# comm_sensing.net
KiCad netlist of a schematic drawn in Altium Designer
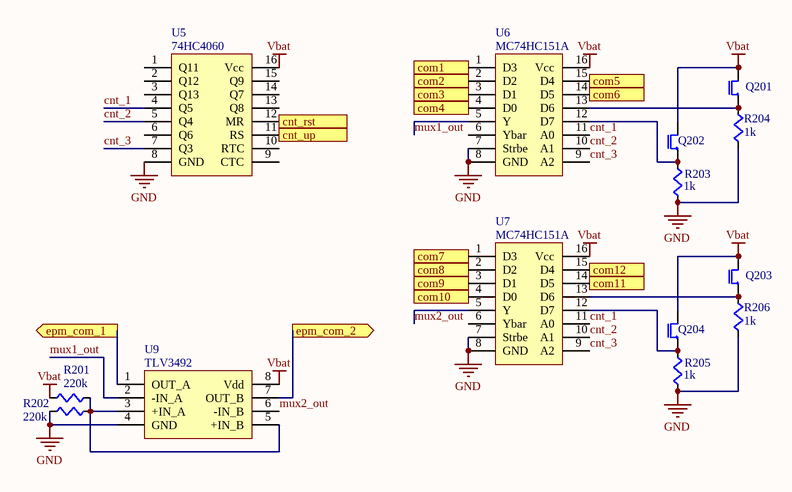
[diagram p0: comm_sensing.SchDoc]

(export (version "E")
  (design (tool "Eeschema 10.0.6"))
  (components
    (comp (ref "Q201")
      (value "PHOTOTRANS")
      (footprint "smd_phototrans")
      (libsource (lib "Components") (part "PHOTOTRANS"))
    )
    (comp (ref "Q202")
      (value "PHOTOTRANS")
      (footprint "smd_phototrans")
      (libsource (lib "Components") (part "PHOTOTRANS"))
    )
    (comp (ref "Q203")
      (value "PHOTOTRANS")
      (footprint "smd_phototrans")
      (libsource (lib "Components") (part "PHOTOTRANS"))
    )
    (comp (ref "Q204")
      (value "PHOTOTRANS")
      (footprint "smd_phototrans")
      (libsource (lib "Components") (part "PHOTOTRANS"))
    )
    (comp (ref "R201")
      (value "220k")
      (footprint "SMD0603")
      (description "Resistor")
      (fields (field (name "Comment") "Res"))
      (libsource (lib "Components") (part "Resistor"))
    )
    (comp (ref "R202")
      (value "220k")
      (footprint "SMD0603")
      (description "Resistor")
      (fields (field (name "Comment") "Res"))
      (libsource (lib "Components") (part "Resistor"))
    )
    (comp (ref "R203")
      (value "1k")
      (footprint "SMD0603")
      (description "Resistor")
      (fields (field (name "Comment") "Res"))
      (libsource (lib "Components") (part "Resistor"))
    )
    (comp (ref "R204")
      (value "1k")
      (footprint "SMD0603")
      (description "Resistor")
      (fields (field (name "Comment") "Res"))
      (libsource (lib "Components") (part "Resistor"))
    )
    (comp (ref "R205")
      (value "1k")
      (footprint "SMD0603")
      (description "Resistor")
      (fields (field (name "Comment") "Res"))
      (libsource (lib "Components") (part "Resistor"))
    )
    (comp (ref "R206")
      (value "1k")
      (footprint "SMD0603")
      (description "Resistor")
      (fields (field (name "Comment") "Res"))
      (libsource (lib "Components") (part "Resistor"))
    )
    (comp (ref "U5")
      (value "74HC4060")
      (footprint "dhvqfn-16")
      (libsource (lib "Components") (part "74HC4060"))
    )
    (comp (ref "U6")
      (value "MC74HC151A")
      (footprint "soic-16")
      (libsource (lib "Components") (part "MC74HC151A"))
    )
    (comp (ref "U7")
      (value "MC74HC151A")
      (footprint "soic-16")
      (libsource (lib "Components") (part "MC74HC151A"))
    )
    (comp (ref "U9") (value "TLV3492") (footprint "sot23-8") (libsource (lib "Components") (part "TLV3492")))
  )
  (nets
    (net (code "1") (name "/cnt_1") (class "Default")
      (node (ref "U5") (pin "4") (pinfunction "Q5_4") (pintype "passive"))
      (node (ref "U6") (pin "11") (pinfunction "A0_11") (pintype "passive"))
      (node (ref "U7") (pin "11") (pinfunction "A0_11") (pintype "passive"))
    )
    (net (code "2") (name "/cnt_2") (class "Default")
      (node (ref "U5") (pin "5") (pinfunction "Q4_5") (pintype "passive"))
      (node (ref "U6") (pin "10") (pinfunction "A1_10") (pintype "passive"))
      (node (ref "U7") (pin "10") (pinfunction "A1_10") (pintype "passive"))
    )
    (net (code "3") (name "/cnt_3") (class "Default")
      (node (ref "U5") (pin "7") (pinfunction "Q3_7") (pintype "passive"))
      (node (ref "U6") (pin "9") (pinfunction "A2_9") (pintype "passive"))
      (node (ref "U7") (pin "9") (pinfunction "A2_9") (pintype "passive"))
    )
    (net (code "4") (name "/cnt_rst") (class "Default")
      (node (ref "U5") (pin "12") (pinfunction "MR_12") (pintype "passive"))
    )
    (net (code "5") (name "/cnt_up") (class "Default")
      (node (ref "U5") (pin "11") (pinfunction "RS_11") (pintype "passive"))
    )
    (net (code "6") (name "/com1") (class "Default")
      (node (ref "U6") (pin "1") (pinfunction "D3_1") (pintype "passive"))
    )
    (net (code "7") (name "/com2") (class "Default")
      (node (ref "U6") (pin "2") (pinfunction "D2_2") (pintype "passive"))
    )
    (net (code "8") (name "/com3") (class "Default")
      (node (ref "U6") (pin "3") (pinfunction "D1_3") (pintype "passive"))
    )
    (net (code "9") (name "/com4") (class "Default")
      (node (ref "U6") (pin "4") (pinfunction "D0_4") (pintype "passive"))
    )
    (net (code "10") (name "/com5") (class "Default")
      (node (ref "U6") (pin "15") (pinfunction "D4_15") (pintype "passive"))
    )
    (net (code "11") (name "/com6") (class "Default")
      (node (ref "U6") (pin "14") (pinfunction "D5_14") (pintype "passive"))
    )
    (net (code "12") (name "/com7") (class "Default")
      (node (ref "U7") (pin "1") (pinfunction "D3_1") (pintype "passive"))
    )
    (net (code "13") (name "/com8") (class "Default")
      (node (ref "U7") (pin "2") (pinfunction "D2_2") (pintype "passive"))
    )
    (net (code "14") (name "/com9") (class "Default")
      (node (ref "U7") (pin "3") (pinfunction "D1_3") (pintype "passive"))
    )
    (net (code "15") (name "/com10") (class "Default")
      (node (ref "U7") (pin "4") (pinfunction "D0_4") (pintype "passive"))
    )
    (net (code "16") (name "/com11") (class "Default")
      (node (ref "U7") (pin "14") (pinfunction "D5_14") (pintype "passive"))
    )
    (net (code "17") (name "/com12") (class "Default")
      (node (ref "U7") (pin "15") (pinfunction "D4_15") (pintype "passive"))
    )
    (net (code "18") (name "/epm_com_1") (class "Default")
      (node (ref "U9") (pin "1") (pinfunction "OUT_A_1") (pintype "passive"))
    )
    (net (code "19") (name "/epm_com_2") (class "Default")
      (node (ref "U9") (pin "7") (pinfunction "OUT_B_7") (pintype "passive"))
    )
    (net (code "20") (name "/mux1_out") (class "Default")
      (node (ref "U6") (pin "5") (pinfunction "Y_5") (pintype "passive"))
      (node (ref "U9") (pin "2") (pinfunction "-IN_A_2") (pintype "passive"))
    )
    (net (code "21") (name "/mux2_out") (class "Default")
      (node (ref "U7") (pin "5") (pinfunction "Y_5") (pintype "passive"))
      (node (ref "U9") (pin "6") (pinfunction "-IN_B_6") (pintype "passive"))
    )
    (net (code "22") (name "GND") (class "Default")
      (node (ref "R202") (pin "2") (pinfunction "2_2") (pintype "passive"))
      (node (ref "R203") (pin "2") (pinfunction "2_2") (pintype "passive"))
      (node (ref "R204") (pin "2") (pinfunction "2_2") (pintype "passive"))
      (node (ref "R205") (pin "2") (pinfunction "2_2") (pintype "passive"))
      (node (ref "R206") (pin "2") (pinfunction "2_2") (pintype "passive"))
      (node (ref "U5") (pin "8") (pinfunction "GND_8") (pintype "passive"))
      (node (ref "U6") (pin "7") (pinfunction "Strbe_7") (pintype "passive"))
      (node (ref "U6") (pin "8") (pinfunction "GND_8") (pintype "passive"))
      (node (ref "U7") (pin "7") (pinfunction "Strbe_7") (pintype "passive"))
      (node (ref "U7") (pin "8") (pinfunction "GND_8") (pintype "passive"))
      (node (ref "U9") (pin "4") (pinfunction "GND_4") (pintype "passive"))
    )
    (net (code "23") (name "Net-(Q201-Emitter)") (class "Default")
      (node (ref "Q201") (pin "2") (pinfunction "Emitter_2") (pintype "passive"))
      (node (ref "R204") (pin "1") (pinfunction "1_1") (pintype "passive"))
      (node (ref "U6") (pin "13") (pinfunction "D6_13") (pintype "passive"))
    )
    (net (code "24") (name "Net-(Q202-Emitter)") (class "Default")
      (node (ref "Q202") (pin "2") (pinfunction "Emitter_2") (pintype "passive"))
      (node (ref "R203") (pin "1") (pinfunction "1_1") (pintype "passive"))
      (node (ref "U6") (pin "12") (pinfunction "D7_12") (pintype "passive"))
    )
    (net (code "25") (name "Net-(Q203-Emitter)") (class "Default")
      (node (ref "Q203") (pin "2") (pinfunction "Emitter_2") (pintype "passive"))
      (node (ref "R206") (pin "1") (pinfunction "1_1") (pintype "passive"))
      (node (ref "U7") (pin "13") (pinfunction "D6_13") (pintype "passive"))
    )
    (net (code "26") (name "Net-(Q204-Emitter)") (class "Default")
      (node (ref "Q204") (pin "2") (pinfunction "Emitter_2") (pintype "passive"))
      (node (ref "R205") (pin "1") (pinfunction "1_1") (pintype "passive"))
      (node (ref "U7") (pin "12") (pinfunction "D7_12") (pintype "passive"))
    )
    (net (code "27") (name "Net-(U9-+IN_A)") (class "Default")
      (node (ref "R201") (pin "1") (pinfunction "1_1") (pintype "passive"))
      (node (ref "R202") (pin "1") (pinfunction "1_1") (pintype "passive"))
      (node (ref "U9") (pin "3") (pinfunction "+IN_A_3") (pintype "passive"))
      (node (ref "U9") (pin "5") (pinfunction "+IN_B_5") (pintype "passive"))
    )
    (net (code "28") (name "Vbat") (class "Default")
      (node (ref "Q201") (pin "1") (pinfunction "Collector_1") (pintype "passive"))
      (node (ref "Q202") (pin "1") (pinfunction "Collector_1") (pintype "passive"))
      (node (ref "Q203") (pin "1") (pinfunction "Collector_1") (pintype "passive"))
      (node (ref "Q204") (pin "1") (pinfunction "Collector_1") (pintype "passive"))
      (node (ref "R201") (pin "2") (pinfunction "2_2") (pintype "passive"))
      (node (ref "U5") (pin "16") (pinfunction "Vcc_16") (pintype "passive"))
      (node (ref "U6") (pin "16") (pinfunction "Vcc_16") (pintype "passive"))
      (node (ref "U7") (pin "16") (pinfunction "Vcc_16") (pintype "passive"))
      (node (ref "U9") (pin "8") (pinfunction "Vdd_8") (pintype "passive"))
    )
    (net (code "29") (name "unconnected-(U5-CTC-Pad9)") (class "Default")
      (node (ref "U5") (pin "9") (pinfunction "CTC_9") (pintype "passive"))
    )
    (net (code "30") (name "unconnected-(U5-Q6-Pad6)") (class "Default")
      (node (ref "U5") (pin "6") (pinfunction "Q6_6") (pintype "passive"))
    )
    (net (code "31") (name "unconnected-(U5-Q7-Pad14)") (class "Default")
      (node (ref "U5") (pin "14") (pinfunction "Q7_14") (pintype "passive"))
    )
    (net (code "32") (name "unconnected-(U5-Q8-Pad13)") (class "Default")
      (node (ref "U5") (pin "13") (pinfunction "Q8_13") (pintype "passive"))
    )
    (net (code "33") (name "unconnected-(U5-Q9-Pad15)") (class "Default")
      (node (ref "U5") (pin "15") (pinfunction "Q9_15") (pintype "passive"))
    )
    (net (code "34") (name "unconnected-(U5-Q11-Pad1)") (class "Default")
      (node (ref "U5") (pin "1") (pinfunction "Q11_1") (pintype "passive"))
    )
    (net (code "35") (name "unconnected-(U5-Q12-Pad2)") (class "Default")
      (node (ref "U5") (pin "2") (pinfunction "Q12_2") (pintype "passive"))
    )
    (net (code "36") (name "unconnected-(U5-Q13-Pad3)") (class "Default")
      (node (ref "U5") (pin "3") (pinfunction "Q13_3") (pintype "passive"))
    )
    (net (code "37") (name "unconnected-(U5-RTC-Pad10)") (class "Default")
      (node (ref "U5") (pin "10") (pinfunction "RTC_10") (pintype "passive"))
    )
    (net (code "38") (name "unconnected-(U6-Ybar-Pad6)") (class "Default")
      (node (ref "U6") (pin "6") (pinfunction "Ybar_6") (pintype "passive"))
    )
    (net (code "39") (name "unconnected-(U7-Ybar-Pad6)") (class "Default")
      (node (ref "U7") (pin "6") (pinfunction "Ybar_6") (pintype "passive"))
    )
  )
)
